# Grove_-_Digital_Infrared_Temperature_Sen.net
KiCad netlist of a schematic drawn in EAGLE
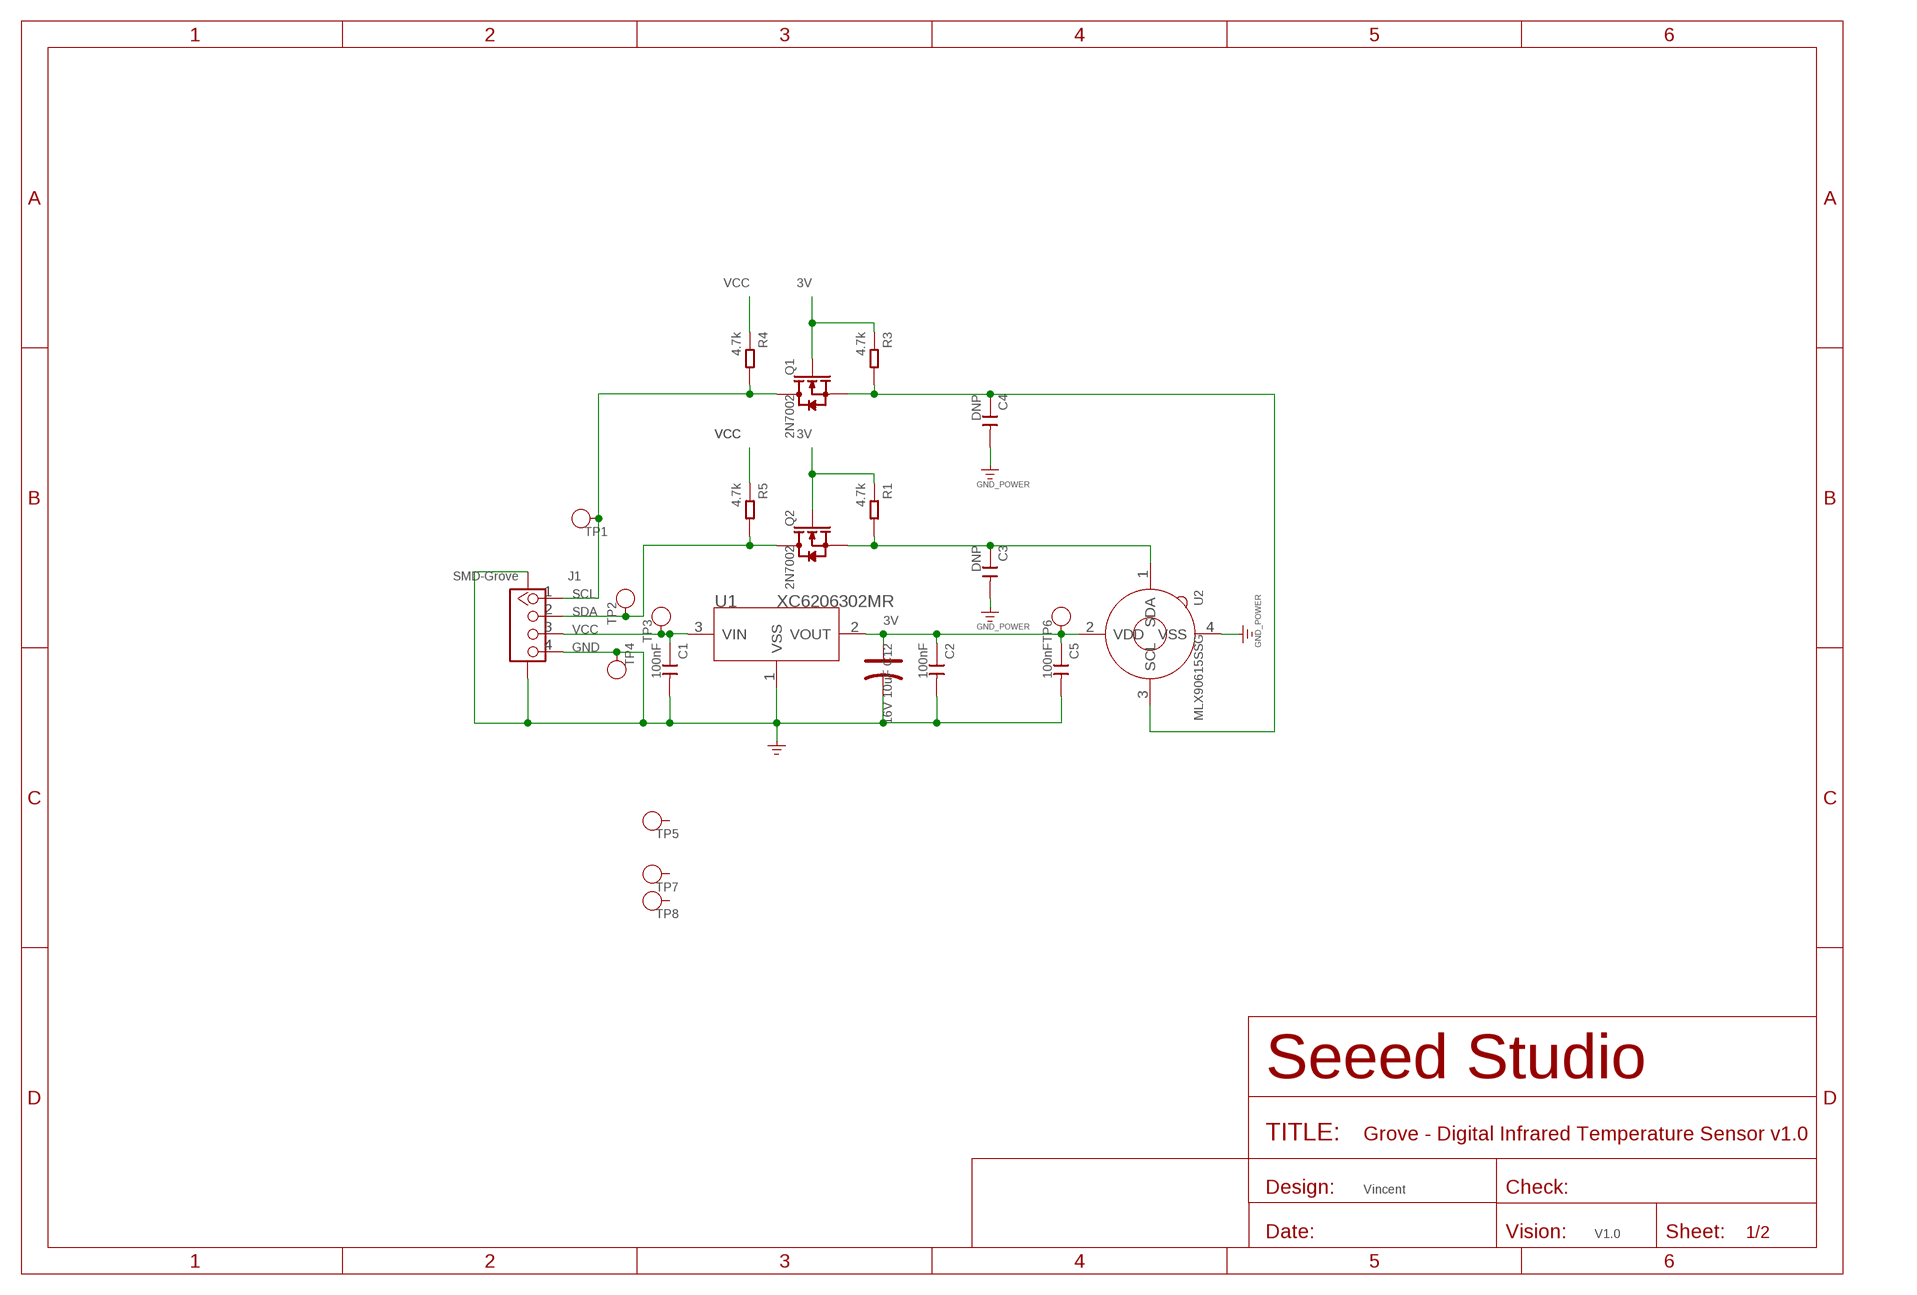
[diagram p0: schematic, sheet 1]
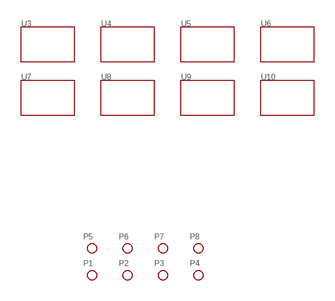
[diagram p1: schematic, sheet 2]

(export (version "E")
  (design (tool "Eeschema 10.0.6"))
  (components
    (comp (ref "P1")
      (value "PAD-MARK")
      (footprint "eagle-import:ROUND-MARK-1.0")
      (fields (field (name "PARTNO") "DNP"))
      (libsource (lib "eagle-import") (part "PAD-MARK"))
    )
    (comp (ref "P2")
      (value "PAD-MARK")
      (footprint "eagle-import:ROUND-MARK-1.0")
      (fields (field (name "PARTNO") "DNP"))
      (libsource (lib "eagle-import") (part "PAD-MARK"))
    )
    (comp (ref "P3")
      (value "PAD-MARK")
      (footprint "eagle-import:ROUND-MARK-1.0")
      (fields (field (name "PARTNO") "DNP"))
      (libsource (lib "eagle-import") (part "PAD-MARK"))
    )
    (comp (ref "P4")
      (value "PAD-MARK")
      (footprint "eagle-import:ROUND-MARK-1.0")
      (fields (field (name "PARTNO") "DNP"))
      (libsource (lib "eagle-import") (part "PAD-MARK"))
    )
    (comp (ref "P5")
      (value "PAD-MARK")
      (footprint "eagle-import:ROUND-MARK-1.0")
      (fields (field (name "PARTNO") "DNP"))
      (libsource (lib "eagle-import") (part "PAD-MARK"))
    )
    (comp (ref "P6")
      (value "PAD-MARK")
      (footprint "eagle-import:ROUND-MARK-1.0")
      (fields (field (name "PARTNO") "DNP"))
      (libsource (lib "eagle-import") (part "PAD-MARK"))
    )
    (comp (ref "P7")
      (value "PAD-MARK")
      (footprint "eagle-import:ROUND-MARK-1.0")
      (fields (field (name "PARTNO") "DNP"))
      (libsource (lib "eagle-import") (part "PAD-MARK"))
    )
    (comp (ref "P8")
      (value "PAD-MARK")
      (footprint "eagle-import:ROUND-MARK-1.0")
      (fields (field (name "PARTNO") "DNP"))
      (libsource (lib "eagle-import") (part "PAD-MARK"))
    )
    (comp (ref "U3")
      (value "TWIG'2U'")
      (footprint "eagle-import:GROVE-TEST-PLATFORM")
      (libsource (lib "eagle-import") (part "TWIG'2U'"))
    )
    (comp (ref "U4")
      (value "TWIG'2U'")
      (footprint "eagle-import:GROVE-TEST-PLATFORM")
      (libsource (lib "eagle-import") (part "TWIG'2U'"))
    )
    (comp (ref "U5")
      (value "TWIG'2U'")
      (footprint "eagle-import:GROVE-TEST-PLATFORM")
      (libsource (lib "eagle-import") (part "TWIG'2U'"))
    )
    (comp (ref "U6")
      (value "TWIG'2U'")
      (footprint "eagle-import:GROVE-TEST-PLATFORM")
      (libsource (lib "eagle-import") (part "TWIG'2U'"))
    )
    (comp (ref "U7")
      (value "TWIG'2U'")
      (footprint "eagle-import:GROVE-TEST-PLATFORM")
      (libsource (lib "eagle-import") (part "TWIG'2U'"))
    )
    (comp (ref "U8")
      (value "TWIG'2U'")
      (footprint "eagle-import:GROVE-TEST-PLATFORM")
      (libsource (lib "eagle-import") (part "TWIG'2U'"))
    )
    (comp (ref "U9")
      (value "TWIG'2U'")
      (footprint "eagle-import:GROVE-TEST-PLATFORM")
      (libsource (lib "eagle-import") (part "TWIG'2U'"))
    )
    (comp (ref "U10")
      (value "TWIG'2U'")
      (footprint "eagle-import:GROVE-TEST-PLATFORM")
      (libsource (lib "eagle-import") (part "TWIG'2U'"))
    )
    (comp (ref "C1")
      (value "100nF")
      (footprint "eagle-import:C0603")
      (libsource (lib "eagle-import") (part "CAP-0603"))
    )
    (comp (ref "C2")
      (value "100nF")
      (footprint "eagle-import:C0603")
      (libsource (lib "eagle-import") (part "CAP-0603"))
    )
    (comp (ref "C3")
      (value "DNP")
      (footprint "eagle-import:C0603")
      (libsource (lib "eagle-import") (part "CAP-0603"))
    )
    (comp (ref "C4")
      (value "DNP")
      (footprint "eagle-import:C0603")
      (libsource (lib "eagle-import") (part "CAP-0603"))
    )
    (comp (ref "C5")
      (value "100nF")
      (footprint "eagle-import:C0603")
      (libsource (lib "eagle-import") (part "CAP-0603"))
    )
    (comp (ref "C12")
      (value "16V 10uF")
      (footprint "eagle-import:AVX-A")
      (libsource (lib "eagle-import") (part "CAP-AVX-A"))
    )
    (comp (ref "J1")
      (value "SMD-Grove")
      (footprint "eagle-import:4P-SMD-2.0")
      (libsource (lib "eagle-import") (part "GROVE-CONNECTOR-SMD'DD'"))
    )
    (comp (ref "Q1")
      (value "2N7002")
      (footprint "eagle-import:SOT23")
      (libsource (lib "eagle-import") (part "MOSFET-N'SOT23'"))
    )
    (comp (ref "Q2")
      (value "2N7002")
      (footprint "eagle-import:SOT23")
      (libsource (lib "eagle-import") (part "MOSFET-N'SOT23'"))
    )
    (comp (ref "R1")
      (value "4.7k")
      (footprint "eagle-import:R0603")
      (libsource (lib "eagle-import") (part "RES-0603"))
    )
    (comp (ref "R3")
      (value "4.7k")
      (footprint "eagle-import:R0603")
      (libsource (lib "eagle-import") (part "RES-0603"))
    )
    (comp (ref "R4")
      (value "4.7k")
      (footprint "eagle-import:R0603")
      (libsource (lib "eagle-import") (part "RES-0603"))
    )
    (comp (ref "R5")
      (value "4.7k")
      (footprint "eagle-import:R0603")
      (libsource (lib "eagle-import") (part "RES-0603"))
    )
    (comp (ref "TP1")
      (value "PAD-TEST-POINT'4545'")
      (footprint "eagle-import:TP-D45MIL")
      (fields (field (name "PARTNO") "DNP"))
      (libsource (lib "eagle-import") (part "PAD-TEST-POINT'4545'"))
    )
    (comp (ref "TP2")
      (value "PAD-TEST-POINT'4545'")
      (footprint "eagle-import:TP-D45MIL")
      (fields (field (name "PARTNO") "DNP"))
      (libsource (lib "eagle-import") (part "PAD-TEST-POINT'4545'"))
    )
    (comp (ref "TP3")
      (value "PAD-TEST-POINT'4545'")
      (footprint "eagle-import:TP-D45MIL")
      (fields (field (name "PARTNO") "DNP"))
      (libsource (lib "eagle-import") (part "PAD-TEST-POINT'4545'"))
    )
    (comp (ref "TP4")
      (value "PAD-TEST-POINT'4545'")
      (footprint "eagle-import:TP-D45MIL")
      (fields (field (name "PARTNO") "DNP"))
      (libsource (lib "eagle-import") (part "PAD-TEST-POINT'4545'"))
    )
    (comp (ref "TP5")
      (value "PAD-TEST-POINT'4545'")
      (footprint "eagle-import:TP-D45MIL")
      (fields (field (name "PARTNO") "DNP"))
      (libsource (lib "eagle-import") (part "PAD-TEST-POINT'4545'"))
    )
    (comp (ref "TP6")
      (value "PAD-TEST-POINT'4545'")
      (footprint "eagle-import:TP-D45MIL")
      (fields (field (name "PARTNO") "DNP"))
      (libsource (lib "eagle-import") (part "PAD-TEST-POINT'4545'"))
    )
    (comp (ref "TP7")
      (value "PAD-TEST-POINT'4545'")
      (footprint "eagle-import:TP-D45MIL")
      (fields (field (name "PARTNO") "DNP"))
      (libsource (lib "eagle-import") (part "PAD-TEST-POINT'4545'"))
    )
    (comp (ref "TP8")
      (value "PAD-TEST-POINT'4545'")
      (footprint "eagle-import:TP-D45MIL")
      (fields (field (name "PARTNO") "DNP"))
      (libsource (lib "eagle-import") (part "PAD-TEST-POINT'4545'"))
    )
    (comp (ref "U1")
      (value "XC6206302MR")
      (footprint "eagle-import:SOT23")
      (libsource (lib "eagle-import") (part "XC6206MR"))
    )
    (comp (ref "U2")
      (value "MLX90615SSG")
      (footprint "eagle-import:4P-D5.4MM_2.7H")
      (libsource (lib "eagle-import") (part "SENSOR-MLX90615"))
    )
  )
  (nets
    (net (code "1") (name "3V") (class "Default")
      (node (ref "C12") (pin "+") (pinfunction "+_+") (pintype "passive"))
      (node (ref "C2") (pin "1") (pinfunction "1_1") (pintype "passive"))
      (node (ref "C5") (pin "1") (pinfunction "1_1") (pintype "passive"))
      (node (ref "Q1") (pin "1") (pinfunction "G_1") (pintype "passive"))
      (node (ref "Q2") (pin "1") (pinfunction "G_1") (pintype "passive"))
      (node (ref "R1") (pin "1") (pinfunction "1_1") (pintype "passive"))
      (node (ref "R3") (pin "1") (pinfunction "1_1") (pintype "passive"))
      (node (ref "TP6") (pin "T") (pinfunction "T_T") (pintype "bidirectional"))
      (node (ref "U1") (pin "2") (pinfunction "VOUT_2") (pintype "output"))
      (node (ref "U2") (pin "2") (pinfunction "VDD_2") (pintype "bidirectional"))
    )
    (net (code "2") (name "GND") (class "Default")
      (node (ref "C1") (pin "2") (pinfunction "2_2") (pintype "passive"))
      (node (ref "C12") (pin "-") (pinfunction "-_-") (pintype "passive"))
      (node (ref "C2") (pin "2") (pinfunction "2_2") (pintype "passive"))
      (node (ref "C3") (pin "2") (pinfunction "2_2") (pintype "passive"))
      (node (ref "C4") (pin "2") (pinfunction "2_2") (pintype "passive"))
      (node (ref "C5") (pin "2") (pinfunction "2_2") (pintype "passive"))
      (node (ref "J1") (pin "4") (pinfunction "4_4") (pintype "bidirectional"))
      (node (ref "J1") (pin "SS1") (pinfunction "SS1_SS1") (pintype "bidirectional"))
      (node (ref "J1") (pin "SS2") (pinfunction "SS2_SS2") (pintype "bidirectional"))
      (node (ref "TP4") (pin "T") (pinfunction "T_T") (pintype "bidirectional"))
      (node (ref "U1") (pin "1") (pinfunction "VSS_1") (pintype "power_in"))
      (node (ref "U2") (pin "4") (pinfunction "VSS_4") (pintype "bidirectional"))
    )
    (net (code "3") (name "Net-(Q1-S)") (class "Default")
      (node (ref "C4") (pin "1") (pinfunction "1_1") (pintype "passive"))
      (node (ref "Q1") (pin "2") (pinfunction "S_2") (pintype "passive"))
      (node (ref "R3") (pin "2") (pinfunction "2_2") (pintype "passive"))
      (node (ref "U2") (pin "3") (pinfunction "SCL_3") (pintype "bidirectional"))
    )
    (net (code "4") (name "Net-(Q2-S)") (class "Default")
      (node (ref "C3") (pin "1") (pinfunction "1_1") (pintype "passive"))
      (node (ref "Q2") (pin "2") (pinfunction "S_2") (pintype "passive"))
      (node (ref "R1") (pin "2") (pinfunction "2_2") (pintype "passive"))
      (node (ref "U2") (pin "1") (pinfunction "SDA_1") (pintype "bidirectional"))
    )
    (net (code "5") (name "SCL") (class "Default")
      (node (ref "J1") (pin "1") (pinfunction "1_1") (pintype "bidirectional"))
      (node (ref "Q1") (pin "3") (pinfunction "D_3") (pintype "passive"))
      (node (ref "R4") (pin "2") (pinfunction "2_2") (pintype "passive"))
      (node (ref "TP1") (pin "T") (pinfunction "T_T") (pintype "bidirectional"))
    )
    (net (code "6") (name "SDA") (class "Default")
      (node (ref "J1") (pin "2") (pinfunction "2_2") (pintype "bidirectional"))
      (node (ref "Q2") (pin "3") (pinfunction "D_3") (pintype "passive"))
      (node (ref "R5") (pin "2") (pinfunction "2_2") (pintype "passive"))
      (node (ref "TP2") (pin "T") (pinfunction "T_T") (pintype "bidirectional"))
    )
    (net (code "7") (name "VCC") (class "Default")
      (node (ref "C1") (pin "1") (pinfunction "1_1") (pintype "passive"))
      (node (ref "J1") (pin "3") (pinfunction "3_3") (pintype "bidirectional"))
      (node (ref "R4") (pin "1") (pinfunction "1_1") (pintype "passive"))
      (node (ref "R5") (pin "1") (pinfunction "1_1") (pintype "passive"))
      (node (ref "TP3") (pin "T") (pinfunction "T_T") (pintype "bidirectional"))
      (node (ref "U1") (pin "3") (pinfunction "VIN_3") (pintype "input"))
    )
    (net (code "8") (name "unconnected-(TP5-PadT)") (class "Default")
      (node (ref "TP5") (pin "T") (pinfunction "T_T") (pintype "bidirectional"))
    )
    (net (code "9") (name "unconnected-(TP7-PadT)") (class "Default")
      (node (ref "TP7") (pin "T") (pinfunction "T_T") (pintype "bidirectional"))
    )
    (net (code "10") (name "unconnected-(TP8-PadT)") (class "Default")
      (node (ref "TP8") (pin "T") (pinfunction "T_T") (pintype "bidirectional"))
    )
  )
)
